# 106729.net
KiCad netlist of a schematic drawn in Altium Designer
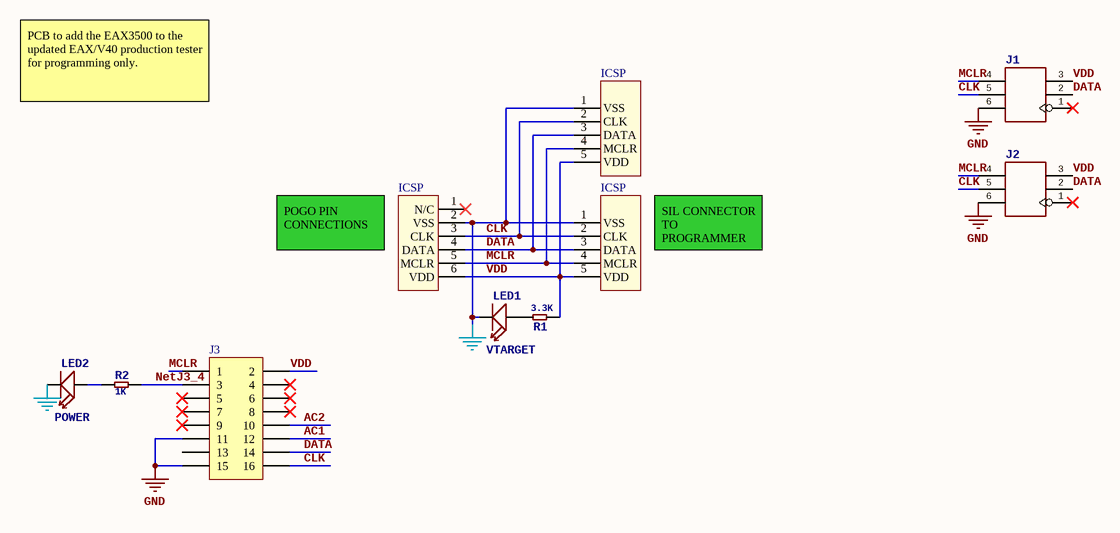
[diagram p0: 106729.SchDoc]

(export (version "E")
  (design (tool "Eeschema 10.0.6"))
  (components
    (comp (ref "ICSP")
      (value "ICSP")
      (footprint "ICSP")
      (description "In-Circuit Serial Programming Header")
      (libsource (lib "") (part "ICSP_1"))
    )
    (comp (ref "J1")
      (value "320020077")
      (footprint "H2X3-2.54")
      (fields (field (name "MPN") "P125-12A1BS116A1"))
      (libsource (lib "Seeed-Connector -2016") (part "DIP-BLACK-MALE-HEADER(2X3P-2.54）-2.54"))
    )
    (comp (ref "J2")
      (value "320020077")
      (footprint "H2X3-2.54")
      (fields (field (name "MPN") "P125-12A1BS116A1"))
      (libsource (lib "Seeed-Connector -2016") (part "DIP-BLACK-MALE-HEADER(2X3P-2.54）-2.54"))
    )
    (comp (ref "J3")
      (value "MHDR2X8")
      (footprint "PcbLib1:16C_2P HEADER")
      (libsource (lib "MyDatabase") (part "MHDR2X8"))
    )
    (comp (ref "LED1")
      (value "VTARGET")
      (footprint "LED2-2.54-D3.0MM")
      (fields (field (name "MPN") "SR302DC"))
      (libsource (lib "Seeed-LED-2016") (part "DIP-LED-RED-RED(2P-D3MM)"))
    )
    (comp (ref "LED2")
      (value "POWER")
      (footprint "LED2-2.54-D3.0MM")
      (fields (field (name "MPN") "SR302DC"))
      (libsource (lib "Seeed-LED-2016") (part "DIP-LED-RED-RED(2P-D3MM)"))
    )
    (comp (ref "R1")
      (value "3.3K")
      (footprint "RESC1206(3216)_N")
      (fields (field (name "MPN") "FHCFR-1/4W-222J") (field (name "Comment") "301020010"))
      (libsource (lib "Seeed-Resistor-2016") (part "DIP-RES-2.2K-5%-1/4W(PR-D2.3XL6.5MM)"))
    )
    (comp (ref "R2")
      (value "1K")
      (footprint "RESC1206(3216)_N")
      (fields (field (name "MPN") "FHCFR-1/4W-222J") (field (name "Comment") "301020010"))
      (libsource (lib "Seeed-Resistor-2016") (part "DIP-RES-2.2K-5%-1/4W(PR-D2.3XL6.5MM)"))
    )
    (comp (ref "SIL")
      (value "ICSP")
      (footprint "SIP5")
      (description "In-Circuit Serial Programming Header")
      (libsource (lib "AltiumIntegratedLibrary") (part "ICSP"))
    )
    (comp (ref "SIL2")
      (value "ICSP")
      (footprint "SIP5")
      (description "In-Circuit Serial Programming Header")
      (libsource (lib "AltiumIntegratedLibrary") (part "ICSP"))
    )
  )
  (nets
    (net (code "1") (name "/AC1") (class "Default")
      (node (ref "J3") (pin "12") (pinfunction "12_12") (pintype "passive"))
    )
    (net (code "2") (name "/AC2") (class "Default")
      (node (ref "J3") (pin "10") (pinfunction "10_10") (pintype "passive"))
    )
    (net (code "3") (name "/CLK") (class "Default")
      (node (ref "ICSP") (pin "3") (pinfunction "CLK_3") (pintype "passive"))
      (node (ref "J1") (pin "5") (pinfunction "5_5") (pintype "passive"))
      (node (ref "J2") (pin "5") (pinfunction "5_5") (pintype "passive"))
      (node (ref "J3") (pin "16") (pinfunction "16_16") (pintype "passive"))
      (node (ref "SIL") (pin "2") (pinfunction "CLK_2") (pintype "passive"))
      (node (ref "SIL2") (pin "2") (pinfunction "CLK_2") (pintype "passive"))
    )
    (net (code "4") (name "/DATA") (class "Default")
      (node (ref "ICSP") (pin "4") (pinfunction "DATA_4") (pintype "passive"))
      (node (ref "J1") (pin "2") (pinfunction "2_2") (pintype "passive"))
      (node (ref "J2") (pin "2") (pinfunction "2_2") (pintype "passive"))
      (node (ref "J3") (pin "14") (pinfunction "14_14") (pintype "passive"))
      (node (ref "SIL") (pin "3") (pinfunction "DATA_3") (pintype "passive"))
      (node (ref "SIL2") (pin "3") (pinfunction "DATA_3") (pintype "passive"))
    )
    (net (code "5") (name "/MCLR") (class "Default")
      (node (ref "ICSP") (pin "5") (pinfunction "MCLR_5") (pintype "passive"))
      (node (ref "J1") (pin "4") (pinfunction "4_4") (pintype "passive"))
      (node (ref "J2") (pin "4") (pinfunction "4_4") (pintype "passive"))
      (node (ref "J3") (pin "1") (pinfunction "1_1") (pintype "passive"))
      (node (ref "SIL") (pin "4") (pinfunction "MCLR_4") (pintype "passive"))
      (node (ref "SIL2") (pin "4") (pinfunction "MCLR_4") (pintype "passive"))
    )
    (net (code "6") (name "/NetJ3_4") (class "Default")
      (node (ref "J3") (pin "3") (pinfunction "3_3") (pintype "passive"))
      (node (ref "R2") (pin "2") (pinfunction "2_2") (pintype "passive"))
    )
    (net (code "7") (name "/VDD") (class "Default")
      (node (ref "ICSP") (pin "6") (pinfunction "VDD_6") (pintype "power_in"))
      (node (ref "J1") (pin "3") (pinfunction "3_3") (pintype "passive"))
      (node (ref "J2") (pin "3") (pinfunction "3_3") (pintype "passive"))
      (node (ref "J3") (pin "2") (pinfunction "2_2") (pintype "passive"))
      (node (ref "R1") (pin "2") (pinfunction "2_2") (pintype "passive"))
      (node (ref "SIL") (pin "5") (pinfunction "VDD_5") (pintype "power_in"))
      (node (ref "SIL2") (pin "5") (pinfunction "VDD_5") (pintype "power_in"))
    )
    (net (code "8") (name "GND") (class "Default")
      (node (ref "ICSP") (pin "2") (pinfunction "VSS_2") (pintype "passive"))
      (node (ref "J1") (pin "6") (pinfunction "6_6") (pintype "passive"))
      (node (ref "J2") (pin "6") (pinfunction "6_6") (pintype "passive"))
      (node (ref "J3") (pin "11") (pinfunction "11_11") (pintype "passive"))
      (node (ref "J3") (pin "15") (pinfunction "15_15") (pintype "passive"))
      (node (ref "LED1") (pin "K") (pinfunction "-_K") (pintype "passive"))
      (node (ref "LED2") (pin "K") (pinfunction "-_K") (pintype "passive"))
      (node (ref "SIL") (pin "1") (pinfunction "VSS_1") (pintype "passive"))
      (node (ref "SIL2") (pin "1") (pinfunction "VSS_1") (pintype "passive"))
    )
    (net (code "9") (name "Net-(LED1-+)") (class "Default")
      (node (ref "LED1") (pin "A") (pinfunction "+_A") (pintype "passive"))
      (node (ref "R1") (pin "1") (pinfunction "1_1") (pintype "passive"))
    )
    (net (code "10") (name "Net-(LED2-+)") (class "Default")
      (node (ref "LED2") (pin "A") (pinfunction "+_A") (pintype "passive"))
      (node (ref "R2") (pin "1") (pinfunction "1_1") (pintype "passive"))
    )
    (net (code "11") (name "unconnected-(ICSP-N{slash}C-Pad1)") (class "Default")
      (node (ref "ICSP") (pin "1") (pinfunction "N/C_1") (pintype "passive+no_connect"))
    )
    (net (code "12") (name "unconnected-(J1-Pad1)") (class "Default")
      (node (ref "J1") (pin "1") (pinfunction "1_1") (pintype "passive+no_connect"))
    )
    (net (code "13") (name "unconnected-(J2-Pad1)") (class "Default")
      (node (ref "J2") (pin "1") (pinfunction "1_1") (pintype "passive+no_connect"))
    )
    (net (code "14") (name "unconnected-(J3-Pad4)") (class "Default")
      (node (ref "J3") (pin "4") (pinfunction "4_4") (pintype "passive+no_connect"))
    )
    (net (code "15") (name "unconnected-(J3-Pad5)") (class "Default")
      (node (ref "J3") (pin "5") (pinfunction "5_5") (pintype "passive+no_connect"))
    )
    (net (code "16") (name "unconnected-(J3-Pad6)") (class "Default")
      (node (ref "J3") (pin "6") (pinfunction "6_6") (pintype "passive+no_connect"))
    )
    (net (code "17") (name "unconnected-(J3-Pad7)") (class "Default")
      (node (ref "J3") (pin "7") (pinfunction "7_7") (pintype "passive+no_connect"))
    )
    (net (code "18") (name "unconnected-(J3-Pad8)") (class "Default")
      (node (ref "J3") (pin "8") (pinfunction "8_8") (pintype "passive+no_connect"))
    )
    (net (code "19") (name "unconnected-(J3-Pad9)") (class "Default")
      (node (ref "J3") (pin "9") (pinfunction "9_9") (pintype "passive+no_connect"))
    )
    (net (code "20") (name "unconnected-(J3-Pad13)") (class "Default")
      (node (ref "J3") (pin "13") (pinfunction "13_13") (pintype "passive"))
    )
  )
)
